# LCDDisplay.net
KiCad netlist of a schematic drawn in EAGLE
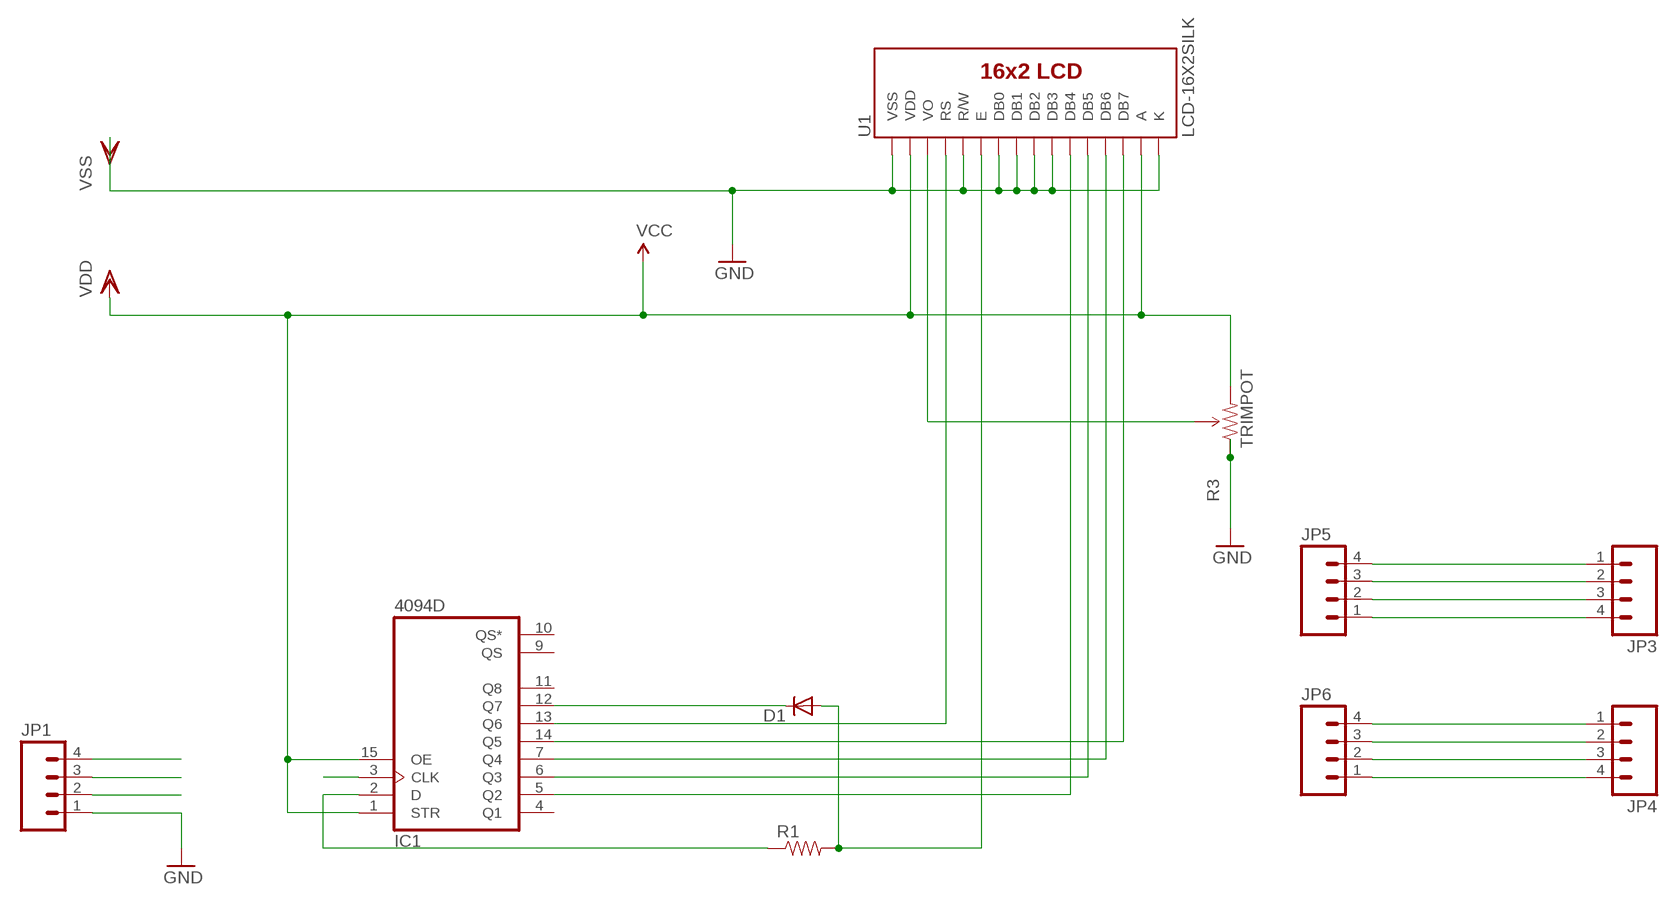
[diagram p0: schematic, sheet 1]

(export (version "E")
  (design (tool "Eeschema 10.0.6"))
  (components
    (comp (ref "D1")
      (value "DIODE1N4148")
      (footprint "eagle-import:DIODE-1N4148")
      (libsource (lib "eagle-import") (part "DIODE1N4148"))
    )
    (comp (ref "IC1")
      (value "4094D")
      (footprint "eagle-import:SO16")
      (libsource (lib "eagle-import") (part "4094D"))
    )
    (comp (ref "JP1")
      (value "M04PTH")
      (footprint "eagle-import:1X04")
      (libsource (lib "eagle-import") (part "M04PTH"))
    )
    (comp (ref "JP3")
      (value "M041.27MM")
      (footprint "eagle-import:1X04-1.27MM")
      (libsource (lib "eagle-import") (part "SparkFun-Connectors_M041.27MM"))
    )
    (comp (ref "JP4")
      (value "M041.27MM")
      (footprint "eagle-import:1X04-1.27MM")
      (libsource (lib "eagle-import") (part "SparkFun-Connectors_M041.27MM"))
    )
    (comp (ref "JP5")
      (value "M04LOCK_LONGPADS")
      (footprint "eagle-import:1X04_LOCK_LONGPADS")
      (libsource (lib "eagle-import") (part "M04LOCK_LONGPADS"))
    )
    (comp (ref "JP6")
      (value "M04LOCK_LONGPADS")
      (footprint "eagle-import:1X04_LOCK_LONGPADS")
      (libsource (lib "eagle-import") (part "M04LOCK_LONGPADS"))
    )
    (comp (ref "R1")
      (value "RESISTORAXIAL-0.3")
      (footprint "eagle-import:AXIAL-0.3")
      (libsource (lib "eagle-import") (part "RESISTORAXIAL-0.3"))
    )
    (comp (ref "R3")
      (value "TRIMPOT")
      (footprint "eagle-import:3362U-2")
      (libsource (lib "eagle-import") (part "TRIMPOT"))
    )
    (comp (ref "U1")
      (value "LCD-16X2SILK")
      (footprint "eagle-import:LCD-16X2")
      (libsource (lib "eagle-import") (part "LCD-16X2SILK"))
    )
  )
  (nets
    (net (code "1") (name "/CLK") (class "Default")
      (node (ref "IC1") (pin "3") (pinfunction "CLK_3") (pintype "input"))
      (node (ref "JP1") (pin "3") (pinfunction "3_3") (pintype "passive"))
    )
    (net (code "2") (name "/DATA") (class "Default")
      (node (ref "IC1") (pin "2") (pinfunction "D_2") (pintype "input"))
      (node (ref "JP1") (pin "4") (pinfunction "4_4") (pintype "passive"))
      (node (ref "R1") (pin "P$1") (pinfunction "1_P$1") (pintype "passive"))
    )
    (net (code "3") (name "GND") (class "Default")
      (node (ref "JP1") (pin "1") (pinfunction "1_1") (pintype "passive"))
      (node (ref "R3") (pin "1") (pinfunction "CCW_1") (pintype "passive"))
      (node (ref "U1") (pin "1") (pinfunction "VSS_1") (pintype "power_in"))
      (node (ref "U1") (pin "10") (pinfunction "DB3_10") (pintype "bidirectional"))
      (node (ref "U1") (pin "16") (pinfunction "K_16") (pintype "power_in"))
      (node (ref "U1") (pin "5") (pinfunction "R/W_5") (pintype "input"))
      (node (ref "U1") (pin "7") (pinfunction "DB0_7") (pintype "bidirectional"))
      (node (ref "U1") (pin "8") (pinfunction "DB1_8") (pintype "bidirectional"))
      (node (ref "U1") (pin "9") (pinfunction "DB2_9") (pintype "bidirectional"))
    )
    (net (code "4") (name "Net-(IC1A-Q2)") (class "Default")
      (node (ref "IC1") (pin "5") (pinfunction "Q2_5") (pintype "output"))
      (node (ref "U1") (pin "11") (pinfunction "DB4_11") (pintype "bidirectional"))
    )
    (net (code "5") (name "Net-(IC1A-Q3)") (class "Default")
      (node (ref "IC1") (pin "6") (pinfunction "Q3_6") (pintype "output"))
      (node (ref "U1") (pin "12") (pinfunction "DB5_12") (pintype "bidirectional"))
    )
    (net (code "6") (name "Net-(IC1A-Q4)") (class "Default")
      (node (ref "IC1") (pin "7") (pinfunction "Q4_7") (pintype "output"))
      (node (ref "U1") (pin "13") (pinfunction "DB6_13") (pintype "bidirectional"))
    )
    (net (code "7") (name "Net-(IC1A-Q5)") (class "Default")
      (node (ref "IC1") (pin "14") (pinfunction "Q5_14") (pintype "output"))
      (node (ref "U1") (pin "14") (pinfunction "DB7_14") (pintype "bidirectional"))
    )
    (net (code "8") (name "Net-(IC1A-Q6)") (class "Default")
      (node (ref "IC1") (pin "13") (pinfunction "Q6_13") (pintype "output"))
      (node (ref "U1") (pin "4") (pinfunction "RS_4") (pintype "input"))
    )
    (net (code "9") (name "Net-(IC1A-Q7)") (class "Default")
      (node (ref "D1") (pin "C") (pinfunction "C_C") (pintype "passive"))
      (node (ref "IC1") (pin "12") (pinfunction "Q7_12") (pintype "output"))
    )
    (net (code "10") (name "Net-(JP3-Pad1)") (class "Default")
      (node (ref "JP3") (pin "1") (pinfunction "1_1") (pintype "passive"))
      (node (ref "JP5") (pin "4") (pinfunction "4_4") (pintype "passive"))
    )
    (net (code "11") (name "Net-(JP3-Pad2)") (class "Default")
      (node (ref "JP3") (pin "2") (pinfunction "2_2") (pintype "passive"))
      (node (ref "JP5") (pin "3") (pinfunction "3_3") (pintype "passive"))
    )
    (net (code "12") (name "Net-(JP3-Pad3)") (class "Default")
      (node (ref "JP3") (pin "3") (pinfunction "3_3") (pintype "passive"))
      (node (ref "JP5") (pin "2") (pinfunction "2_2") (pintype "passive"))
    )
    (net (code "13") (name "Net-(JP3-Pad4)") (class "Default")
      (node (ref "JP3") (pin "4") (pinfunction "4_4") (pintype "passive"))
      (node (ref "JP5") (pin "1") (pinfunction "1_1") (pintype "passive"))
    )
    (net (code "14") (name "Net-(JP4-Pad1)") (class "Default")
      (node (ref "JP4") (pin "1") (pinfunction "1_1") (pintype "passive"))
      (node (ref "JP6") (pin "4") (pinfunction "4_4") (pintype "passive"))
    )
    (net (code "15") (name "Net-(JP4-Pad2)") (class "Default")
      (node (ref "JP4") (pin "2") (pinfunction "2_2") (pintype "passive"))
      (node (ref "JP6") (pin "3") (pinfunction "3_3") (pintype "passive"))
    )
    (net (code "16") (name "Net-(JP4-Pad3)") (class "Default")
      (node (ref "JP4") (pin "3") (pinfunction "3_3") (pintype "passive"))
      (node (ref "JP6") (pin "2") (pinfunction "2_2") (pintype "passive"))
    )
    (net (code "17") (name "Net-(JP4-Pad4)") (class "Default")
      (node (ref "JP4") (pin "4") (pinfunction "4_4") (pintype "passive"))
      (node (ref "JP6") (pin "1") (pinfunction "1_1") (pintype "passive"))
    )
    (net (code "18") (name "Net-(R1-2)") (class "Default")
      (node (ref "D1") (pin "A") (pinfunction "A_A") (pintype "passive"))
      (node (ref "R1") (pin "P$2") (pinfunction "2_P$2") (pintype "passive"))
      (node (ref "U1") (pin "6") (pinfunction "E_6") (pintype "input"))
    )
    (net (code "19") (name "Net-(R3-WIPER)") (class "Default")
      (node (ref "R3") (pin "2") (pinfunction "WIPER_2") (pintype "passive"))
      (node (ref "U1") (pin "3") (pinfunction "VO_3") (pintype "bidirectional"))
    )
    (net (code "20") (name "VCC") (class "Default")
      (node (ref "IC1") (pin "1") (pinfunction "STR_1") (pintype "input"))
      (node (ref "IC1") (pin "15") (pinfunction "OE_15") (pintype "input"))
      (node (ref "JP1") (pin "2") (pinfunction "2_2") (pintype "passive"))
      (node (ref "R3") (pin "3") (pinfunction "CW_3") (pintype "passive"))
      (node (ref "U1") (pin "15") (pinfunction "A_15") (pintype "power_in"))
      (node (ref "U1") (pin "2") (pinfunction "VDD_2") (pintype "power_in"))
    )
    (net (code "21") (name "unconnected-(IC1A-Q1-Pad4)") (class "Default")
      (node (ref "IC1") (pin "4") (pinfunction "Q1_4") (pintype "output"))
    )
    (net (code "22") (name "unconnected-(IC1A-Q8-Pad11)") (class "Default")
      (node (ref "IC1") (pin "11") (pinfunction "Q8_11") (pintype "output"))
    )
    (net (code "23") (name "unconnected-(IC1A-QS*-Pad10)") (class "Default")
      (node (ref "IC1") (pin "10") (pinfunction "QS*_10") (pintype "output"))
    )
    (net (code "24") (name "unconnected-(IC1A-QS-Pad9)") (class "Default")
      (node (ref "IC1") (pin "9") (pinfunction "QS_9") (pintype "output"))
    )
  )
)
